# Sheet_3_-_Alims.net
KiCad netlist of a schematic drawn in Altium Designer
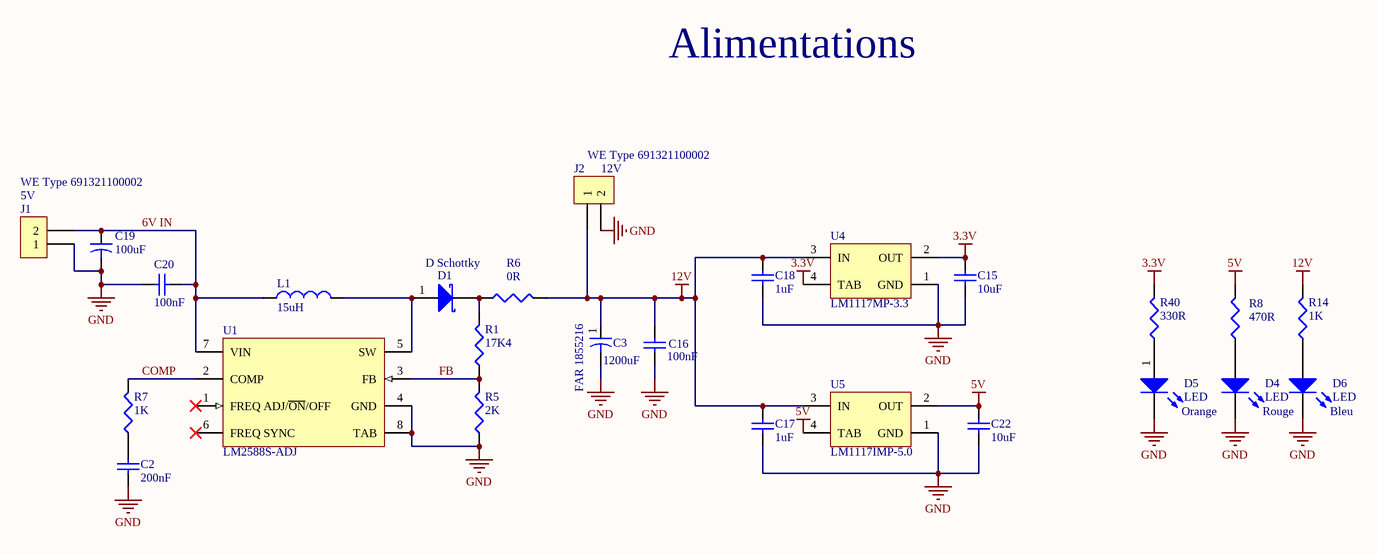
[diagram p0: Sheet 3 - Alims.SchDoc]

(export (version "E")
  (design (tool "Eeschema 10.0.6"))
  (components
    (comp (ref "C2")
      (value "200nF")
      (footprint "pcb_peb_1:C0805")
      (description "Capacitor 0805")
      (fields (field (name "PUBLISHER") "Altium Limited"))
      (libsource (lib "Miscellaneous Devices") (part "Cap"))
    )
    (comp (ref "C3")
      (value "1200uF")
      (footprint "CAPA_D10_E5")
      (description "EEUFM1C122L")
      (fields (field (name "RÉFÉRENCE COMMANDE") "FAR 1855216") (field (name "PUBLISHER") "Altium Limited"))
      (libsource (lib "Miscellaneous Devices") (part "Cap2"))
    )
    (comp (ref "C15")
      (value "10uF")
      (footprint "pcb_peb_1:C0805")
      (description "Capacitor 0805")
      (fields (field (name "PUBLISHER") "Altium Limited"))
      (libsource (lib "Miscellaneous Devices") (part "Cap"))
    )
    (comp (ref "C16")
      (value "100nF")
      (footprint "pcb_peb_1:C0805")
      (description "Capacitor 0805")
      (fields (field (name "PUBLISHER") "Altium Limited"))
      (libsource (lib "Miscellaneous Devices") (part "Cap"))
    )
    (comp (ref "C17")
      (value "1uF")
      (footprint "pcb_peb_1:C0805")
      (description "Capacitor 0805")
      (fields (field (name "PUBLISHER") "Altium Limited"))
      (libsource (lib "Miscellaneous Devices") (part "Cap"))
    )
    (comp (ref "C18")
      (value "1uF")
      (footprint "pcb_peb_1:C0805")
      (description "Capacitor 0805")
      (fields (field (name "PUBLISHER") "Altium Limited"))
      (libsource (lib "Miscellaneous Devices") (part "Cap"))
    )
    (comp (ref "C19")
      (value "100uF")
      (footprint "C1206")
      (description "Capacitor 1206")
      (fields (field (name "PUBLISHER") "Altium Limited"))
      (libsource (lib "") (part "Cap2_1"))
    )
    (comp (ref "C20")
      (value "100nF")
      (footprint "pcb_peb_1:C0805")
      (description "Capacitor 0805")
      (fields (field (name "PUBLISHER") "Altium Limited"))
      (libsource (lib "Miscellaneous Devices") (part "Cap"))
    )
    (comp (ref "C22")
      (value "10uF")
      (footprint "pcb_peb_1:C0805")
      (description "Capacitor 0805")
      (fields (field (name "PUBLISHER") "Altium Limited"))
      (libsource (lib "Miscellaneous Devices") (part "Cap"))
    )
    (comp (ref "D1")
      (value "D Schottky")
      (footprint "D0805")
      (description "Schottky Diode 0805")
      (fields (field (name "PUBLISHER") "Altium Limited"))
      (libsource (lib "Miscellaneous Devices") (part "D Schottky"))
    )
    (comp (ref "D4")
      (value "LED")
      (footprint "LED 0805")
      (description "Typical RED, GREEN, YELLOW, AMBER GaAs LED 0805")
      (fields (field (name "ALTIUM_VALUE") "Rouge") (field (name "PUBLISHER") "Altium Limited"))
      (libsource (lib "Miscellaneous Devices") (part "LED2"))
    )
    (comp (ref "D5")
      (value "LED")
      (footprint "LED 0805")
      (description "Typical RED, GREEN, YELLOW, AMBER GaAs LED 0805")
      (fields (field (name "ALTIUM_VALUE") "Orange") (field (name "PUBLISHER") "Altium Limited"))
      (libsource (lib "") (part "LED2_1"))
    )
    (comp (ref "D6")
      (value "LED")
      (footprint "LED 0805")
      (description "Typical RED, GREEN, YELLOW, AMBER GaAs LED 0805")
      (fields (field (name "ALTIUM_VALUE") "Bleu") (field (name "PUBLISHER") "Altium Limited"))
      (libsource (lib "Miscellaneous Devices") (part "LED2"))
    )
    (comp (ref "J1")
      (value "WE Type 691321100002")
      (footprint "691321100002")
      (description "WR-TBL Terminal block - serie 3211 - 3.50 mm")
      (fields
        (field (name "MANUFACTURER") "Würth Elektronik eiSos GmbH")
        (field (name "PARTNO") "691321100002")
        (field (name "VALUE1") "5V")
        (field (name "CREATED BY") "Karrer Zheng")
      )
      (libsource (lib "6913211000xx") (part "WE-Terminal Blocks Plugable Type 691321100002"))
    )
    (comp (ref "J2")
      (value "WE Type 691321100002")
      (footprint "691321100002")
      (description "WR-TBL Terminal block - serie 3211 - 3.50 mm")
      (fields
        (field (name "MANUFACTURER") "Würth Elektronik eiSos GmbH")
        (field (name "VALUE1") "12V")
        (field (name "CREATED BY") "Karrer Zheng")
      )
      (libsource (lib "") (part "WE-Terminal Blocks Plugable Type 691321100002_1"))
    )
    (comp (ref "L1")
      (value "15uH")
      (footprint "Inductance 4.06 x 4.45")
      (description "SRP4020TA-150M")
      (fields (field (name "PUBLISHER") "Altium Limited"))
      (libsource (lib "Miscellaneous Devices") (part "Inductor"))
    )
    (comp (ref "R1")
      (value "17K4")
      (footprint "0805")
      (description "Resistor 0805")
      (fields (field (name "PUBLISHER") "Altium Limited"))
      (libsource (lib "Miscellaneous Devices") (part "Res3"))
    )
    (comp (ref "R5")
      (value "2K")
      (footprint "0805")
      (description "Resistor 0805")
      (fields (field (name "PUBLISHER") "Altium Limited"))
      (libsource (lib "Miscellaneous Devices") (part "Res3"))
    )
    (comp (ref "R6")
      (value "0R")
      (footprint "0805")
      (description "Resistor 0805")
      (fields (field (name "PUBLISHER") "Altium Limited"))
      (libsource (lib "Miscellaneous Devices") (part "Res3"))
    )
    (comp (ref "R7")
      (value "1K")
      (footprint "0805")
      (description "Resistor 0805")
      (fields (field (name "PUBLISHER") "Altium Limited"))
      (libsource (lib "Miscellaneous Devices") (part "Res3"))
    )
    (comp (ref "R8")
      (value "470R")
      (footprint "0805")
      (description "Resistor 0805")
      (fields (field (name "PUBLISHER") "Altium Limited"))
      (libsource (lib "Miscellaneous Devices") (part "Res3"))
    )
    (comp (ref "R14")
      (value "1K")
      (footprint "0805")
      (description "Resistor 0805")
      (fields (field (name "PUBLISHER") "Altium Limited"))
      (libsource (lib "Miscellaneous Devices") (part "Res3"))
    )
    (comp (ref "R40")
      (value "330R")
      (footprint "0805")
      (description "Resistor 0805")
      (fields (field (name "PUBLISHER") "Altium Limited"))
      (libsource (lib "Miscellaneous Devices") (part "Res3"))
    )
    (comp (ref "U1")
      (value "LM2588S-ADJ")
      (footprint "TS7B_N")
      (description "SIMPLE SWITCHER 5A Flyback Regulator with Shutdown")
      (fields
        (field (name "MANUFACTURER") "National Semiconductor")
        (field (name "DIGIKEYPARTNUMBER") "LM2588S-ADJ-ND")
        (field (name "PUBLISHER") "Altium Limited")
      )
      (libsource (lib "NSC Switcher") (part "LM2588S-ADJ"))
    )
    (comp (ref "U4")
      (value "LM1117MP-3.3")
      (footprint "MP04A_N")
      (description "800mA Low-Dropout Linear Regulator")
      (fields
        (field (name "MANUFACTURER") "National Semiconductor")
        (field (name "DIGIKEYPARTNUMBER") "LM1117MP-3.3CT-ND")
        (field (name "PUBLISHER") "Altium Limited")
      )
      (libsource (lib "NSC LDO") (part "LM1117MP-3.3"))
    )
    (comp (ref "U5")
      (value "LM1117IMP-5.0")
      (footprint "MP04A_N")
      (description "800mA Low-Dropout Linear Regulator")
      (fields
        (field (name "MANUFACTURER") "National Semiconductor")
        (field (name "DIGIKEYPARTNUMBER") "LM1117IMP-5.0CT-ND")
        (field (name "PUBLISHER") "Altium Limited")
      )
      (libsource (lib "NSC LDO") (part "LM1117IMP-5.0"))
    )
  )
  (nets
    (net (code "1") (name "/6V IN") (class "Default")
      (node (ref "C19") (pin "1") (pinfunction "1_1") (pintype "passive"))
      (node (ref "C20") (pin "2") (pinfunction "2_2") (pintype "passive"))
      (node (ref "J1") (pin "1") (pinfunction "2_1") (pintype "passive"))
      (node (ref "L1") (pin "1") (pinfunction "1_1") (pintype "passive"))
      (node (ref "U1") (pin "7") (pinfunction "VIN_7") (pintype "power_in"))
    )
    (net (code "2") (name "/COMP") (class "Default")
      (node (ref "R7") (pin "2") (pinfunction "2_2") (pintype "passive"))
      (node (ref "U1") (pin "2") (pinfunction "COMP_2") (pintype "passive"))
    )
    (net (code "3") (name "/FB") (class "Default")
      (node (ref "R1") (pin "1") (pinfunction "1_1") (pintype "passive"))
      (node (ref "R5") (pin "2") (pinfunction "2_2") (pintype "passive"))
      (node (ref "U1") (pin "3") (pinfunction "FB_3") (pintype "input"))
    )
    (net (code "4") (name "3.3V") (class "Default")
      (node (ref "C15") (pin "2") (pinfunction "2_2") (pintype "passive"))
      (node (ref "R40") (pin "2") (pinfunction "2_2") (pintype "passive"))
      (node (ref "U4") (pin "2") (pinfunction "OUT_2") (pintype "power_in"))
      (node (ref "U4") (pin "4") (pinfunction "TAB_4") (pintype "power_in"))
    )
    (net (code "5") (name "5V") (class "Default")
      (node (ref "C22") (pin "2") (pinfunction "2_2") (pintype "passive"))
      (node (ref "R8") (pin "2") (pinfunction "2_2") (pintype "passive"))
      (node (ref "U5") (pin "2") (pinfunction "OUT_2") (pintype "power_in"))
      (node (ref "U5") (pin "4") (pinfunction "TAB_4") (pintype "power_in"))
    )
    (net (code "6") (name "12V") (class "Default")
      (node (ref "C16") (pin "2") (pinfunction "2_2") (pintype "passive"))
      (node (ref "C17") (pin "2") (pinfunction "2_2") (pintype "passive"))
      (node (ref "C18") (pin "2") (pinfunction "2_2") (pintype "passive"))
      (node (ref "C3") (pin "1") (pinfunction "1_1") (pintype "passive"))
      (node (ref "J2") (pin "1") (pinfunction "1_1") (pintype "passive"))
      (node (ref "R14") (pin "2") (pinfunction "2_2") (pintype "passive"))
      (node (ref "R6") (pin "2") (pinfunction "2_2") (pintype "passive"))
      (node (ref "U4") (pin "3") (pinfunction "IN_3") (pintype "power_in"))
      (node (ref "U5") (pin "3") (pinfunction "IN_3") (pintype "power_in"))
    )
    (net (code "7") (name "GND") (class "Default")
      (node (ref "C15") (pin "1") (pinfunction "1_1") (pintype "passive"))
      (node (ref "C16") (pin "1") (pinfunction "1_1") (pintype "passive"))
      (node (ref "C17") (pin "1") (pinfunction "1_1") (pintype "passive"))
      (node (ref "C18") (pin "1") (pinfunction "1_1") (pintype "passive"))
      (node (ref "C19") (pin "2") (pinfunction "2_2") (pintype "passive"))
      (node (ref "C2") (pin "1") (pinfunction "1_1") (pintype "passive"))
      (node (ref "C20") (pin "1") (pinfunction "1_1") (pintype "passive"))
      (node (ref "C22") (pin "1") (pinfunction "1_1") (pintype "passive"))
      (node (ref "C3") (pin "2") (pinfunction "2_2") (pintype "passive"))
      (node (ref "D4") (pin "2") (pinfunction "K_2") (pintype "passive"))
      (node (ref "D5") (pin "2") (pinfunction "K_2") (pintype "passive"))
      (node (ref "D6") (pin "2") (pinfunction "K_2") (pintype "passive"))
      (node (ref "J1") (pin "2") (pinfunction "1_2") (pintype "passive"))
      (node (ref "J2") (pin "2") (pinfunction "2_2") (pintype "passive"))
      (node (ref "R5") (pin "1") (pinfunction "1_1") (pintype "passive"))
      (node (ref "U1") (pin "4") (pinfunction "GND_4") (pintype "power_in"))
      (node (ref "U1") (pin "8") (pinfunction "TAB_8") (pintype "passive"))
      (node (ref "U4") (pin "1") (pinfunction "GND_1") (pintype "power_in"))
      (node (ref "U5") (pin "1") (pinfunction "GND_1") (pintype "power_in"))
    )
    (net (code "8") (name "Net-(C2-Pad2)") (class "Default")
      (node (ref "C2") (pin "2") (pinfunction "2_2") (pintype "passive"))
      (node (ref "R7") (pin "1") (pinfunction "1_1") (pintype "passive"))
    )
    (net (code "9") (name "Net-(D1-A)") (class "Default")
      (node (ref "D1") (pin "1") (pinfunction "A_1") (pintype "passive"))
      (node (ref "L1") (pin "2") (pinfunction "2_2") (pintype "passive"))
      (node (ref "U1") (pin "5") (pinfunction "SW_5") (pintype "power_in"))
    )
    (net (code "10") (name "Net-(D1-K)") (class "Default")
      (node (ref "D1") (pin "2") (pinfunction "K_2") (pintype "passive"))
      (node (ref "R1") (pin "2") (pinfunction "2_2") (pintype "passive"))
      (node (ref "R6") (pin "1") (pinfunction "1_1") (pintype "passive"))
    )
    (net (code "11") (name "Net-(D4-A)") (class "Default")
      (node (ref "D4") (pin "1") (pinfunction "A_1") (pintype "passive"))
      (node (ref "R8") (pin "1") (pinfunction "1_1") (pintype "passive"))
    )
    (net (code "12") (name "Net-(D5-A)") (class "Default")
      (node (ref "D5") (pin "1") (pinfunction "A_1") (pintype "passive"))
      (node (ref "R40") (pin "1") (pinfunction "1_1") (pintype "passive"))
    )
    (net (code "13") (name "Net-(D6-A)") (class "Default")
      (node (ref "D6") (pin "1") (pinfunction "A_1") (pintype "passive"))
      (node (ref "R14") (pin "1") (pinfunction "1_1") (pintype "passive"))
    )
    (net (code "14") (name "unconnected-(U1-FREQ_ADJ{slash}~{ON}{slash}OFF-Pad1)") (class "Default")
      (node (ref "U1") (pin "1") (pinfunction "FREQ_ADJ/~{ON}/OFF_1") (pintype "input+no_connect"))
    )
    (net (code "15") (name "unconnected-(U1-FREQ_SYNC-Pad6)") (class "Default")
      (node (ref "U1") (pin "6") (pinfunction "FREQ_SYNC_6") (pintype "passive+no_connect"))
    )
  )
)
